# SCH_uCompute_VGA_adaptor_2025-12-26.net
KiCad netlist of a schematic drawn in EasyEDA
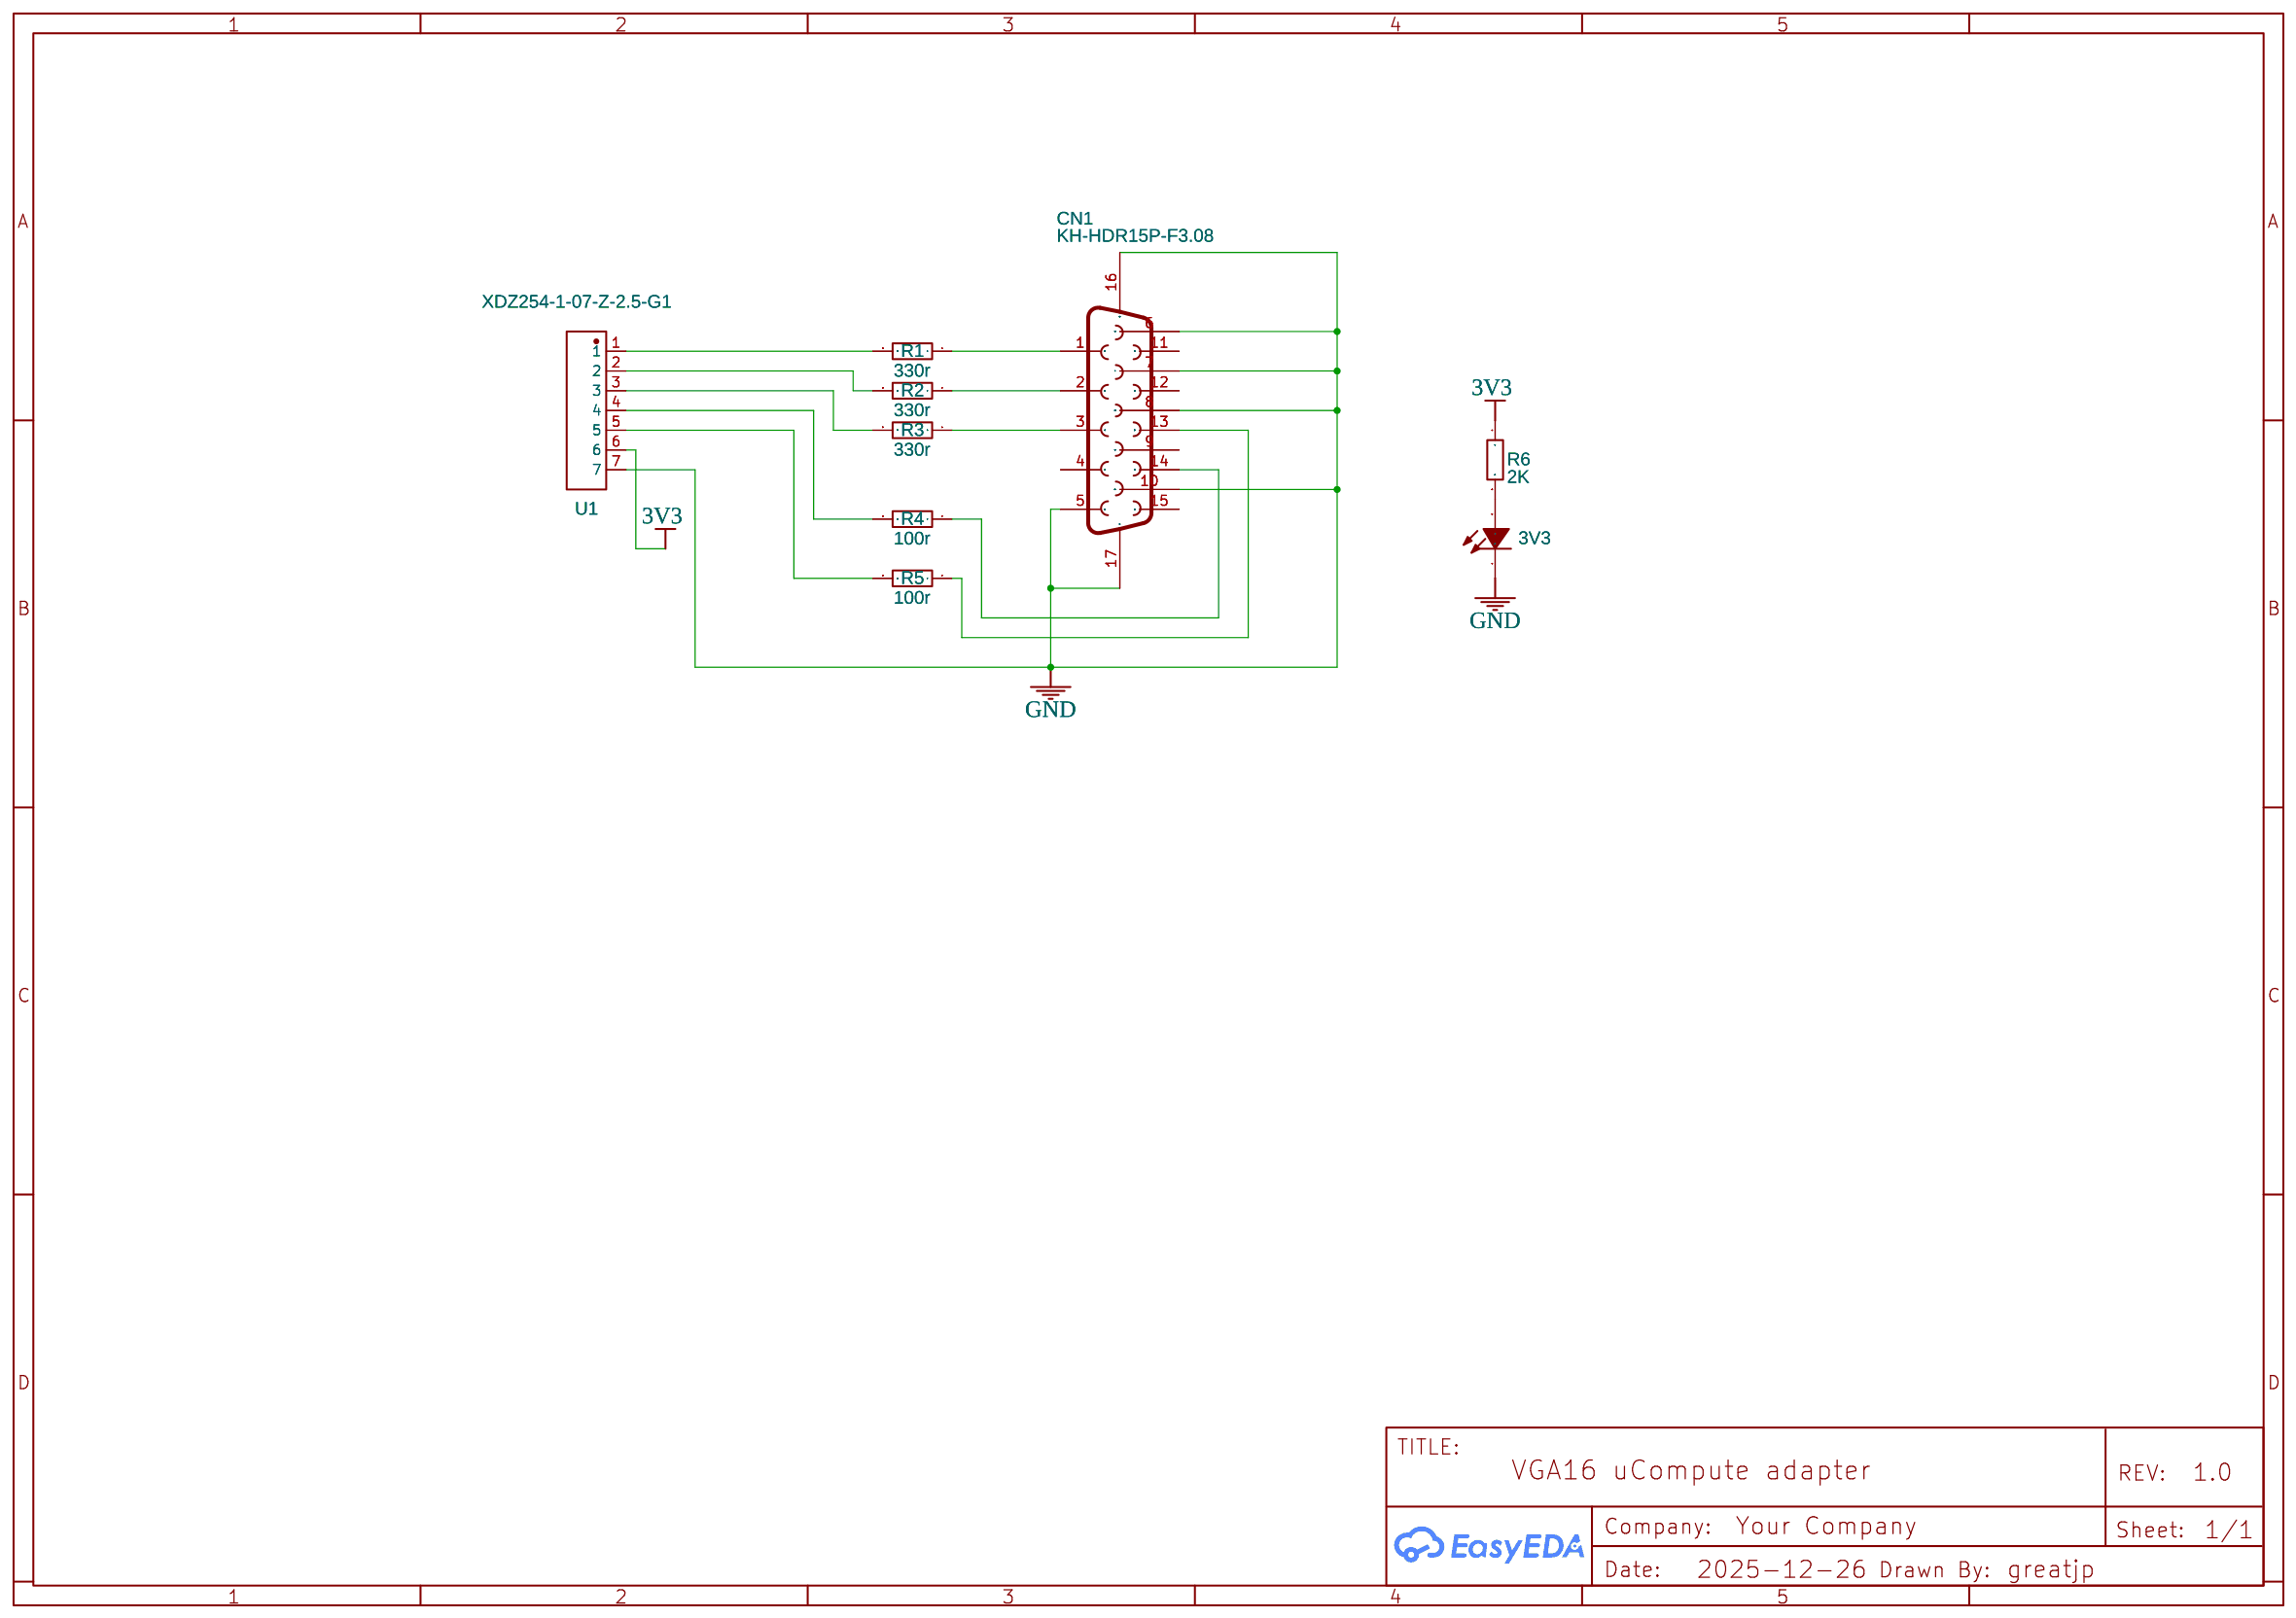
[diagram p0: schematic sheet]

(export (version "E")
  (design (tool "Eeschema 10.0.6"))
  (components
    (comp (ref "3V3")
      (value "XL-1206QPC")
      (fields (field (name "Manufacturer") "LCSC"))
      (libsource (lib "") (part "XL-1206QPC"))
    )
    (comp (ref "CN1")
      (value "KH-HDR15P-F3.08")
      (fields (field (name "Manufacturer") "kinghelm(金航标)"))
      (libsource (lib "") (part "KH-HDR15P-F3.08"))
    )
    (comp (ref "R1")
      (value "330r")
      (fields (field (name "Manufacturer Part") "RC0805DR-071KL") (field (name "Manufacturer") "YAGEO(国巨)"))
      (libsource (lib "") (part "RC0805DR-071KL"))
    )
    (comp (ref "R2")
      (value "330r")
      (fields (field (name "Manufacturer Part") "RC0805DR-071KL") (field (name "Manufacturer") "YAGEO(国巨)"))
      (libsource (lib "") (part "RC0805DR-071KL"))
    )
    (comp (ref "R3")
      (value "330r")
      (fields (field (name "Manufacturer Part") "RC0805DR-071KL") (field (name "Manufacturer") "YAGEO(国巨)"))
      (libsource (lib "") (part "RC0805DR-071KL"))
    )
    (comp (ref "R4")
      (value "100r")
      (fields (field (name "Manufacturer Part") "RC0805DR-071KL") (field (name "Manufacturer") "YAGEO(国巨)"))
      (libsource (lib "") (part "RC0805DR-071KL"))
    )
    (comp (ref "R5")
      (value "100r")
      (fields (field (name "Manufacturer Part") "RC0805DR-071KL") (field (name "Manufacturer") "YAGEO(国巨)"))
      (libsource (lib "") (part "RC0805DR-071KL"))
    )
    (comp (ref "R6")
      (value "2K")
      (fields (field (name "Manufacturer Part") "RC0805DR-071KL") (field (name "Manufacturer") "YAGEO(国巨)"))
      (libsource (lib "") (part "RC0805DR-071KL_1"))
    )
    (comp (ref "U1")
      (value "XDZ254-1-07-Z-2.5-G1")
      (fields (field (name "Manufacturer") "XUNDA(讯答)"))
      (libsource (lib "") (part "XDZ254-1-07-Z-2.5-G1"))
    )
  )
  (nets
    (net (code "1") (name "3V3") (class "Default")
      (node (ref "R6") (pin "1") (pinfunction "1_1") (pintype "unspecified"))
      (node (ref "U1") (pin "6") (pinfunction "6_6") (pintype "unspecified"))
    )
    (net (code "2") (name "GND") (class "Default")
      (node (ref "3V3") (pin "1") (pinfunction "K_1") (pintype "unspecified"))
      (node (ref "CN1") (pin "10") (pinfunction "10_10") (pintype "unspecified"))
      (node (ref "CN1") (pin "16") (pinfunction "16_16") (pintype "unspecified"))
      (node (ref "CN1") (pin "17") (pinfunction "17_17") (pintype "unspecified"))
      (node (ref "CN1") (pin "5") (pinfunction "5_5") (pintype "unspecified"))
      (node (ref "CN1") (pin "6") (pinfunction "6_6") (pintype "unspecified"))
      (node (ref "CN1") (pin "7") (pinfunction "7_7") (pintype "unspecified"))
      (node (ref "CN1") (pin "8") (pinfunction "8_8") (pintype "unspecified"))
      (node (ref "U1") (pin "7") (pinfunction "7_7") (pintype "unspecified"))
    )
    (net (code "3") (name "Net-(3V3-A)") (class "Default")
      (node (ref "3V3") (pin "2") (pinfunction "A_2") (pintype "unspecified"))
      (node (ref "R6") (pin "2") (pinfunction "2_2") (pintype "unspecified"))
    )
    (net (code "4") (name "Net-(CN1-Pad1)") (class "Default")
      (node (ref "CN1") (pin "1") (pinfunction "1_1") (pintype "unspecified"))
      (node (ref "R1") (pin "1") (pinfunction "1_1") (pintype "unspecified"))
    )
    (net (code "5") (name "Net-(CN1-Pad2)") (class "Default")
      (node (ref "CN1") (pin "2") (pinfunction "2_2") (pintype "unspecified"))
      (node (ref "R2") (pin "1") (pinfunction "1_1") (pintype "unspecified"))
    )
    (net (code "6") (name "Net-(CN1-Pad3)") (class "Default")
      (node (ref "CN1") (pin "3") (pinfunction "3_3") (pintype "unspecified"))
      (node (ref "R3") (pin "1") (pinfunction "1_1") (pintype "unspecified"))
    )
    (net (code "7") (name "Net-(CN1-Pad13)") (class "Default")
      (node (ref "CN1") (pin "13") (pinfunction "13_13") (pintype "unspecified"))
      (node (ref "R5") (pin "1") (pinfunction "1_1") (pintype "unspecified"))
    )
    (net (code "8") (name "Net-(CN1-Pad14)") (class "Default")
      (node (ref "CN1") (pin "14") (pinfunction "14_14") (pintype "unspecified"))
      (node (ref "R4") (pin "1") (pinfunction "1_1") (pintype "unspecified"))
    )
    (net (code "9") (name "Net-(R1-Pad2)") (class "Default")
      (node (ref "R1") (pin "2") (pinfunction "2_2") (pintype "unspecified"))
      (node (ref "U1") (pin "1") (pinfunction "1_1") (pintype "unspecified"))
    )
    (net (code "10") (name "Net-(R2-Pad2)") (class "Default")
      (node (ref "R2") (pin "2") (pinfunction "2_2") (pintype "unspecified"))
      (node (ref "U1") (pin "2") (pinfunction "2_2") (pintype "unspecified"))
    )
    (net (code "11") (name "Net-(R3-Pad2)") (class "Default")
      (node (ref "R3") (pin "2") (pinfunction "2_2") (pintype "unspecified"))
      (node (ref "U1") (pin "3") (pinfunction "3_3") (pintype "unspecified"))
    )
    (net (code "12") (name "Net-(R4-Pad2)") (class "Default")
      (node (ref "R4") (pin "2") (pinfunction "2_2") (pintype "unspecified"))
      (node (ref "U1") (pin "4") (pinfunction "4_4") (pintype "unspecified"))
    )
    (net (code "13") (name "Net-(R5-Pad2)") (class "Default")
      (node (ref "R5") (pin "2") (pinfunction "2_2") (pintype "unspecified"))
      (node (ref "U1") (pin "5") (pinfunction "5_5") (pintype "unspecified"))
    )
    (net (code "14") (name "unconnected-(CN1-Pad4)") (class "Default")
      (node (ref "CN1") (pin "4") (pinfunction "4_4") (pintype "unspecified"))
    )
    (net (code "15") (name "unconnected-(CN1-Pad9)") (class "Default")
      (node (ref "CN1") (pin "9") (pinfunction "9_9") (pintype "unspecified"))
    )
    (net (code "16") (name "unconnected-(CN1-Pad11)") (class "Default")
      (node (ref "CN1") (pin "11") (pinfunction "11_11") (pintype "unspecified"))
    )
    (net (code "17") (name "unconnected-(CN1-Pad12)") (class "Default")
      (node (ref "CN1") (pin "12") (pinfunction "12_12") (pintype "unspecified"))
    )
    (net (code "18") (name "unconnected-(CN1-Pad15)") (class "Default")
      (node (ref "CN1") (pin "15") (pinfunction "15_15") (pintype "unspecified"))
    )
  )
)
